# kicker.net
KiCad netlist of a schematic drawn in EAGLE
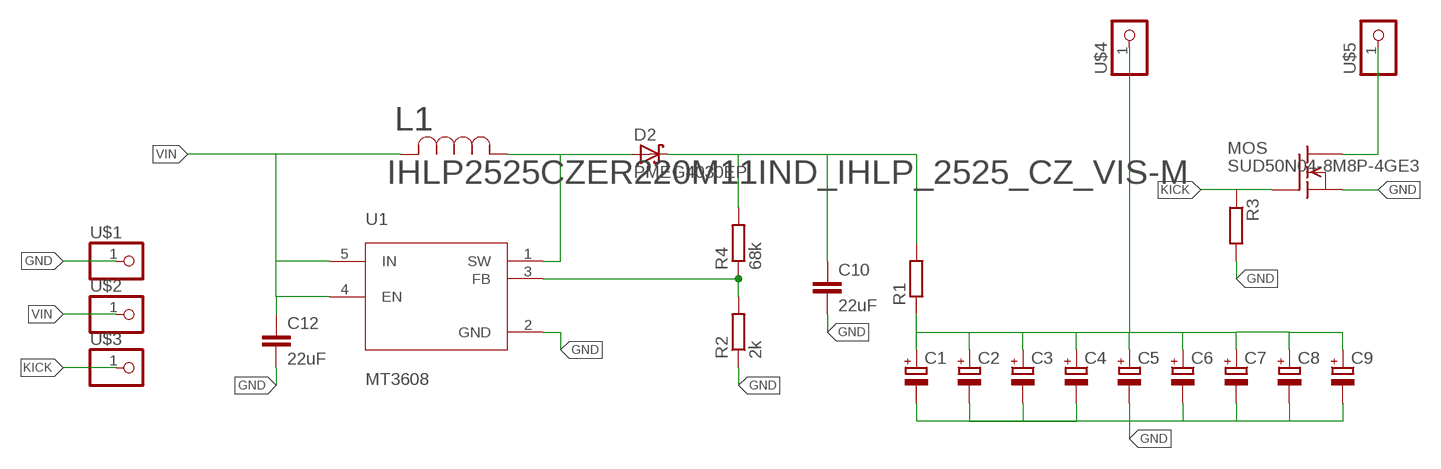
[diagram p0: schematic, sheet 1]

(export (version "E")
  (design (tool "Eeschema 10.0.6"))
  (components
    (comp (ref "C1")
      (value "CPOL-EU153CLV-1010")
      (footprint "eagle-import:153CLV-1010")
      (libsource (lib "eagle-import") (part "CPOL-EU153CLV-1010"))
    )
    (comp (ref "C2")
      (value "CPOL-EU153CLV-1010")
      (footprint "eagle-import:153CLV-1010")
      (libsource (lib "eagle-import") (part "CPOL-EU153CLV-1010"))
    )
    (comp (ref "C3")
      (value "CPOL-EU153CLV-1010")
      (footprint "eagle-import:153CLV-1010")
      (libsource (lib "eagle-import") (part "CPOL-EU153CLV-1010"))
    )
    (comp (ref "C4")
      (value "CPOL-EU153CLV-1010")
      (footprint "eagle-import:153CLV-1010")
      (libsource (lib "eagle-import") (part "CPOL-EU153CLV-1010"))
    )
    (comp (ref "C5")
      (value "CPOL-EU153CLV-1010")
      (footprint "eagle-import:153CLV-1010")
      (libsource (lib "eagle-import") (part "CPOL-EU153CLV-1010"))
    )
    (comp (ref "C6")
      (value "CPOL-EU153CLV-1010")
      (footprint "eagle-import:153CLV-1010")
      (libsource (lib "eagle-import") (part "CPOL-EU153CLV-1010"))
    )
    (comp (ref "C7")
      (value "CPOL-EU153CLV-1010")
      (footprint "eagle-import:153CLV-1010")
      (libsource (lib "eagle-import") (part "CPOL-EU153CLV-1010"))
    )
    (comp (ref "C8")
      (value "CPOL-EU153CLV-1010")
      (footprint "eagle-import:153CLV-1010")
      (libsource (lib "eagle-import") (part "CPOL-EU153CLV-1010"))
    )
    (comp (ref "C9")
      (value "CPOL-EU153CLV-1010")
      (footprint "eagle-import:153CLV-1010")
      (libsource (lib "eagle-import") (part "CPOL-EU153CLV-1010"))
    )
    (comp (ref "C10")
      (value "22uF")
      (footprint "eagle-import:C0805")
      (libsource (lib "eagle-import") (part "C-EUC0805"))
    )
    (comp (ref "C12")
      (value "22uF")
      (footprint "eagle-import:C0805")
      (libsource (lib "eagle-import") (part "C-EUC0805"))
    )
    (comp (ref "D2")
      (value "PMEG4030EP")
      (footprint "eagle-import:SOD128")
      (libsource (lib "eagle-import") (part "PMEG4030EP"))
    )
    (comp (ref "L1")
      (value "IHLP2525CZER220M11IND_IHLP_2525_CZ_VIS-M")
      (footprint "eagle-import:IND_IHLP_2525_CZ_VIS-M")
      (fields (field (name "MANUFACTURER_PART_NUMBER") "IHLP2525CZER220M11"))
      (libsource (lib "eagle-import") (part "IHLP2525CZER220M11IND_IHLP_2525_CZ_VIS-M"))
    )
    (comp (ref "MOS")
      (value "SUD50N04-8M8P-4GE3")
      (footprint "eagle-import:TO252")
      (libsource (lib "eagle-import") (part "SUD50N04-8M8P-4GE3"))
    )
    (comp (ref "R1")
      (value "R-EU_R2010")
      (footprint "eagle-import:R2010")
      (libsource (lib "eagle-import") (part "R-EU_R2010"))
    )
    (comp (ref "R2")
      (value "2k")
      (footprint "eagle-import:M0805")
      (libsource (lib "eagle-import") (part "resistor_R-EU_M0805"))
    )
    (comp (ref "R3")
      (value "R-EU_M0805")
      (footprint "eagle-import:M0805")
      (libsource (lib "eagle-import") (part "resistor_R-EU_M0805"))
    )
    (comp (ref "R4")
      (value "68k")
      (footprint "eagle-import:M0805")
      (libsource (lib "eagle-import") (part "resistor_R-EU_M0805"))
    )
    (comp (ref "U$1")
      (value "CONNEC_1X01PAD")
      (footprint "eagle-import:1_PAD")
      (libsource (lib "eagle-import") (part "CONNEC_1X01PAD"))
    )
    (comp (ref "U$2")
      (value "CONNEC_1X01PAD")
      (footprint "eagle-import:1_PAD")
      (libsource (lib "eagle-import") (part "CONNEC_1X01PAD"))
    )
    (comp (ref "U$3")
      (value "CONNEC_1X01PAD")
      (footprint "eagle-import:1_PAD")
      (libsource (lib "eagle-import") (part "CONNEC_1X01PAD"))
    )
    (comp (ref "U$4")
      (value "CONNEC_1X01PAD")
      (footprint "eagle-import:1_PAD")
      (libsource (lib "eagle-import") (part "CONNEC_1X01PAD"))
    )
    (comp (ref "U$5")
      (value "CONNEC_1X01PAD")
      (footprint "eagle-import:1_PAD")
      (libsource (lib "eagle-import") (part "CONNEC_1X01PAD"))
    )
    (comp (ref "U1")
      (value "MT3608")
      (footprint "eagle-import:SOT95P280X145-6N")
      (fields (field (name "MF") "Aerosemi Technology Co., Ltd"))
      (libsource (lib "eagle-import") (part "MT3608"))
    )
  )
  (nets
    (net (code "1") (name "GND") (class "Default")
      (node (ref "C1") (pin "-") (pinfunction "-_-") (pintype "passive"))
      (node (ref "C10") (pin "2") (pinfunction "2_2") (pintype "passive"))
      (node (ref "C12") (pin "2") (pinfunction "2_2") (pintype "passive"))
      (node (ref "C2") (pin "-") (pinfunction "-_-") (pintype "passive"))
      (node (ref "C3") (pin "-") (pinfunction "-_-") (pintype "passive"))
      (node (ref "C4") (pin "-") (pinfunction "-_-") (pintype "passive"))
      (node (ref "C5") (pin "-") (pinfunction "-_-") (pintype "passive"))
      (node (ref "C6") (pin "-") (pinfunction "-_-") (pintype "passive"))
      (node (ref "C7") (pin "-") (pinfunction "-_-") (pintype "passive"))
      (node (ref "C8") (pin "-") (pinfunction "-_-") (pintype "passive"))
      (node (ref "C9") (pin "-") (pinfunction "-_-") (pintype "passive"))
      (node (ref "MOS") (pin "2") (pinfunction "S_2") (pintype "passive"))
      (node (ref "R2") (pin "1") (pinfunction "1_1") (pintype "passive"))
      (node (ref "R3") (pin "2") (pinfunction "2_2") (pintype "passive"))
      (node (ref "U$1") (pin "1") (pinfunction "1_1") (pintype "passive"))
      (node (ref "U1") (pin "2") (pinfunction "GND_2") (pintype "power_in"))
    )
    (net (code "2") (name "KICK") (class "Default")
      (node (ref "MOS") (pin "1") (pinfunction "G_1") (pintype "passive"))
      (node (ref "R3") (pin "1") (pinfunction "1_1") (pintype "passive"))
      (node (ref "U$3") (pin "1") (pinfunction "1_1") (pintype "passive"))
    )
    (net (code "3") (name "Net-(C1-Pad+)") (class "Default")
      (node (ref "C1") (pin "+") (pinfunction "+_+") (pintype "passive"))
      (node (ref "C2") (pin "+") (pinfunction "+_+") (pintype "passive"))
      (node (ref "C3") (pin "+") (pinfunction "+_+") (pintype "passive"))
      (node (ref "C4") (pin "+") (pinfunction "+_+") (pintype "passive"))
      (node (ref "C5") (pin "+") (pinfunction "+_+") (pintype "passive"))
      (node (ref "C6") (pin "+") (pinfunction "+_+") (pintype "passive"))
      (node (ref "C7") (pin "+") (pinfunction "+_+") (pintype "passive"))
      (node (ref "C8") (pin "+") (pinfunction "+_+") (pintype "passive"))
      (node (ref "C9") (pin "+") (pinfunction "+_+") (pintype "passive"))
      (node (ref "R1") (pin "1") (pinfunction "1_1") (pintype "passive"))
      (node (ref "U$4") (pin "1") (pinfunction "1_1") (pintype "passive"))
    )
    (net (code "4") (name "Net-(D2-A)") (class "Default")
      (node (ref "D2") (pin "2") (pinfunction "A_2") (pintype "passive"))
      (node (ref "L1") (pin "1") (pinfunction "1_1") (pintype "passive"))
      (node (ref "U1") (pin "1") (pinfunction "SW_1") (pintype "output"))
    )
    (net (code "5") (name "Net-(D2-K)") (class "Default")
      (node (ref "C10") (pin "1") (pinfunction "1_1") (pintype "passive"))
      (node (ref "D2") (pin "1") (pinfunction "K_1") (pintype "passive"))
      (node (ref "R1") (pin "2") (pinfunction "2_2") (pintype "passive"))
      (node (ref "R4") (pin "2") (pinfunction "2_2") (pintype "passive"))
    )
    (net (code "6") (name "Net-(MOS-D)") (class "Default")
      (node (ref "MOS") (pin "3") (pinfunction "D_3") (pintype "passive"))
      (node (ref "U$5") (pin "1") (pinfunction "1_1") (pintype "passive"))
    )
    (net (code "7") (name "Net-(U1-FB)") (class "Default")
      (node (ref "R2") (pin "2") (pinfunction "2_2") (pintype "passive"))
      (node (ref "R4") (pin "1") (pinfunction "1_1") (pintype "passive"))
      (node (ref "U1") (pin "3") (pinfunction "FB_3") (pintype "input"))
    )
    (net (code "8") (name "VIN") (class "Default")
      (node (ref "C12") (pin "1") (pinfunction "1_1") (pintype "passive"))
      (node (ref "L1") (pin "2") (pinfunction "2_2") (pintype "passive"))
      (node (ref "U$2") (pin "1") (pinfunction "1_1") (pintype "passive"))
      (node (ref "U1") (pin "4") (pinfunction "EN_4") (pintype "input"))
      (node (ref "U1") (pin "5") (pinfunction "IN_5") (pintype "input"))
    )
  )
)
